# Sheet2.net
KiCad netlist of a schematic drawn in Altium Designer
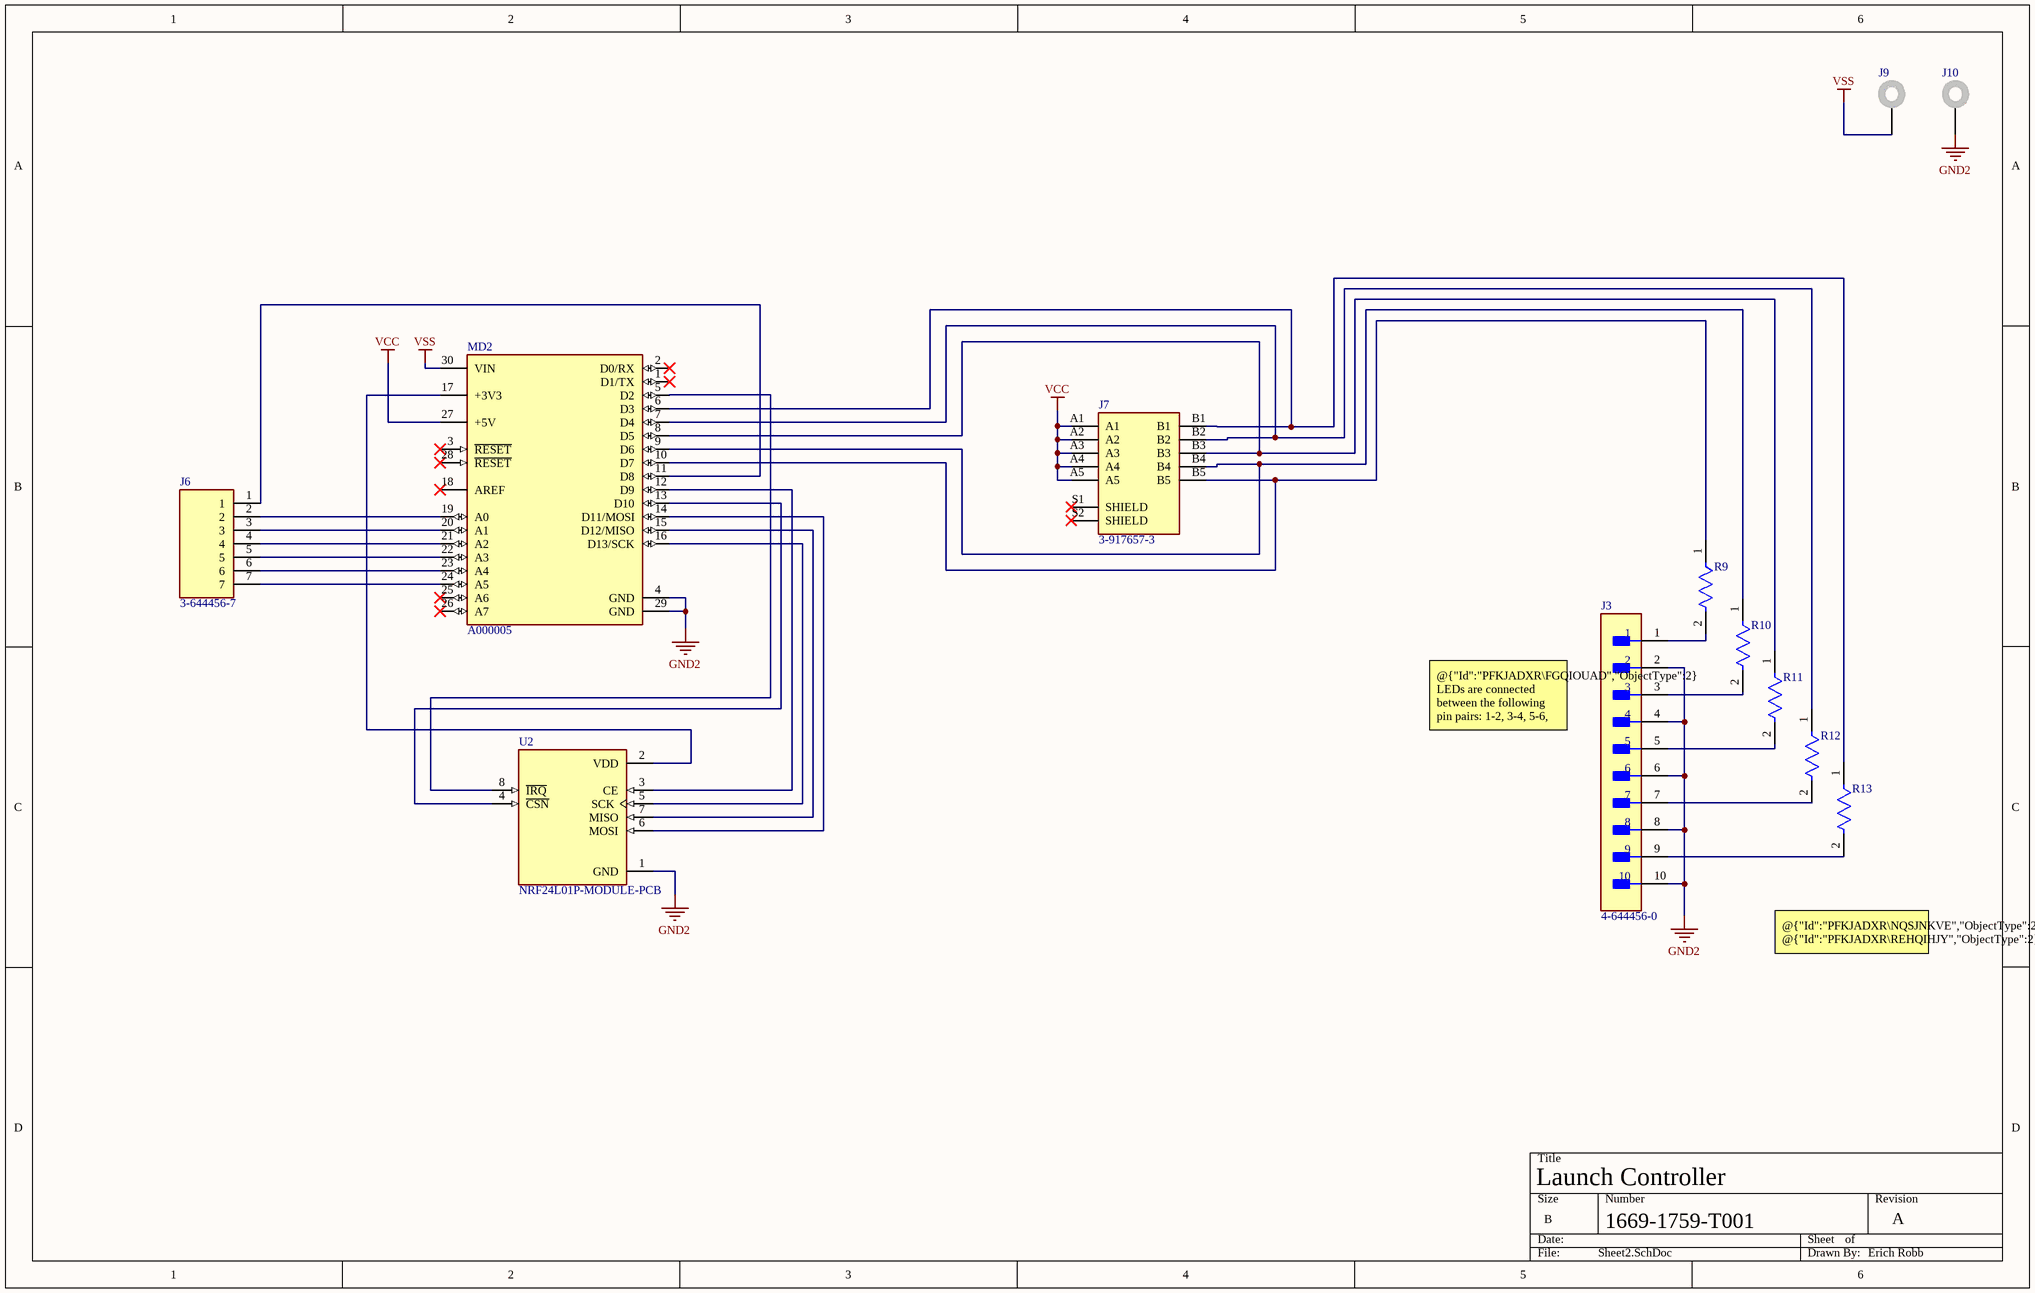
[diagram p0: Sheet2.SchDoc]

(export (version "E")
  (design (tool "Eeschema 10.0.6"))
  (components
    (comp (ref "J3")
      (value "4-644456-0")
      (footprint "FP-4-644456-0-MFG")
      (description "Conn Unshrouded Header HDR 10 POS 2.54mm Solder ST Top Entry Thru-Hole Bag/Box")
      (libsource (lib "Erich Robb") (part "aee40dc8b284c03a16094555aa210be"))
    )
    (comp (ref "J6")
      (value "3-644456-7")
      (footprint "TE_3-644456-7")
      (description "Header; 0.1 in. (Centerline); White (Housing); Polyester; 7; UL 94V-0")
      (fields (field (name "DIGI-KEY_PART_NUMBER") "A31117-ND") (field (name "MF") "TE Connectivity"))
      (libsource (lib "Erich Robb") (part "3-644456-7"))
    )
    (comp (ref "J7")
      (value "3-917657-3")
      (footprint "TE_3-917657-3")
      (libsource (lib "Erich Robb") (part "3-917657-3"))
    )
    (comp (ref "J9")
      (value "575-8")
      (footprint "KSTN-575-8")
      (description "Non-Insulated Jack, Through Hole, RoHS, Bulk")
      (fields (field (name "MANUFACTURER") "Keystone"))
      (libsource (lib "Altium Content Vault") (part "KSTN-575-8"))
    )
    (comp (ref "J10")
      (value "575-8")
      (footprint "KSTN-575-8")
      (description "Non-Insulated Jack, Through Hole, RoHS, Bulk")
      (fields (field (name "MANUFACTURER") "Keystone"))
      (libsource (lib "Altium Content Vault") (part "KSTN-575-8"))
    )
    (comp (ref "MD2")
      (value "A000005")
      (footprint "FP-A000005-MFG")
      (description "ARDUINO NANO ATMEGA328 EVAL BRD")
      (libsource (lib "Altium Content Vault") (part "d190c066e99afd1c6882cf92e11b2cc"))
    )
    (comp (ref "R9")
      (value "CRGCQ1206J330R")
      (footprint "FP-CRGCQ1206-IPC_C")
      (description "CRGCQ1206 330Ω 0.25W 5% ±100ppm/°C 200V")
      (fields (field (name "TOLERANCE") "0.05") (field (name "MANUFACTURER") "TE Connectivity"))
      (libsource (lib "Altium Content Vault") (part "1029c3af85768c4190bb7ad29bc67b5"))
    )
    (comp (ref "R10")
      (value "CRGCQ1206J330R")
      (footprint "FP-CRGCQ1206-IPC_C")
      (description "CRGCQ1206 330Ω 0.25W 5% ±100ppm/°C 200V")
      (fields (field (name "TOLERANCE") "0.05") (field (name "MANUFACTURER") "TE Connectivity"))
      (libsource (lib "Altium Content Vault") (part "1029c3af85768c4190bb7ad29bc67b5"))
    )
    (comp (ref "R11")
      (value "CRGCQ1206J330R")
      (footprint "FP-CRGCQ1206-IPC_C")
      (description "CRGCQ1206 330Ω 0.25W 5% ±100ppm/°C 200V")
      (fields (field (name "TOLERANCE") "0.05") (field (name "MANUFACTURER") "TE Connectivity"))
      (libsource (lib "Altium Content Vault") (part "1029c3af85768c4190bb7ad29bc67b5"))
    )
    (comp (ref "R12")
      (value "CRGCQ1206J330R")
      (footprint "FP-CRGCQ1206-IPC_C")
      (description "CRGCQ1206 330Ω 0.25W 5% ±100ppm/°C 200V")
      (fields (field (name "TOLERANCE") "0.05") (field (name "MANUFACTURER") "TE Connectivity"))
      (libsource (lib "Altium Content Vault") (part "1029c3af85768c4190bb7ad29bc67b5"))
    )
    (comp (ref "R13")
      (value "CRGCQ1206J330R")
      (footprint "FP-CRGCQ1206-IPC_C")
      (description "CRGCQ1206 330Ω 0.25W 5% ±100ppm/°C 200V")
      (fields (field (name "TOLERANCE") "0.05") (field (name "MANUFACTURER") "TE Connectivity"))
      (libsource (lib "Altium Content Vault") (part "1029c3af85768c4190bb7ad29bc67b5"))
    )
    (comp (ref "U2")
      (value "NRF24L01P-MODULE-PCB")
      (footprint "XCVR_NRF24L01P-MODULE-PCB")
      (description "- Transceiver For Use With nRF24L01+")
      (fields (field (name "MF") "Nordic Semiconductor"))
      (libsource (lib "Erich Robb") (part "NRF24L01P-MODULE-PCB"))
    )
  )
  (nets
    (net (code "1") (name "GND2") (class "Default")
      (node (ref "J10") (pin "1") (pinfunction "1_1") (pintype "passive"))
      (node (ref "J3") (pin "10") (pinfunction "10_10") (pintype "passive"))
      (node (ref "J3") (pin "2") (pinfunction "2_2") (pintype "passive"))
      (node (ref "J3") (pin "4") (pinfunction "4_4") (pintype "passive"))
      (node (ref "J3") (pin "6") (pinfunction "6_6") (pintype "passive"))
      (node (ref "J3") (pin "8") (pinfunction "8_8") (pintype "passive"))
      (node (ref "MD2") (pin "29") (pinfunction "GND_29") (pintype "power_in"))
      (node (ref "MD2") (pin "4") (pinfunction "GND_4") (pintype "power_in"))
      (node (ref "U2") (pin "1") (pinfunction "GND_1") (pintype "power_in"))
    )
    (net (code "2") (name "Net-(J3-Pad1)") (class "Default")
      (node (ref "J3") (pin "1") (pinfunction "1_1") (pintype "passive"))
      (node (ref "R9") (pin "2") (pinfunction "2_2") (pintype "passive"))
    )
    (net (code "3") (name "Net-(J3-Pad3)") (class "Default")
      (node (ref "J3") (pin "3") (pinfunction "3_3") (pintype "passive"))
      (node (ref "R10") (pin "2") (pinfunction "2_2") (pintype "passive"))
    )
    (net (code "4") (name "Net-(J3-Pad5)") (class "Default")
      (node (ref "J3") (pin "5") (pinfunction "5_5") (pintype "passive"))
      (node (ref "R11") (pin "2") (pinfunction "2_2") (pintype "passive"))
    )
    (net (code "5") (name "Net-(J3-Pad7)") (class "Default")
      (node (ref "J3") (pin "7") (pinfunction "7_7") (pintype "passive"))
      (node (ref "R12") (pin "2") (pinfunction "2_2") (pintype "passive"))
    )
    (net (code "6") (name "Net-(J3-Pad9)") (class "Default")
      (node (ref "J3") (pin "9") (pinfunction "9_9") (pintype "passive"))
      (node (ref "R13") (pin "2") (pinfunction "2_2") (pintype "passive"))
    )
    (net (code "7") (name "Net-(MD2-+3V3)") (class "Default")
      (node (ref "MD2") (pin "17") (pinfunction "+3V3_17") (pintype "power_in"))
      (node (ref "U2") (pin "2") (pinfunction "VDD_2") (pintype "power_in"))
    )
    (net (code "8") (name "Net-(MD2-A0)") (class "Default")
      (node (ref "J6") (pin "2") (pinfunction "2_2") (pintype "passive"))
      (node (ref "MD2") (pin "19") (pinfunction "A0_19") (pintype "bidirectional"))
    )
    (net (code "9") (name "Net-(MD2-A1)") (class "Default")
      (node (ref "J6") (pin "3") (pinfunction "3_3") (pintype "passive"))
      (node (ref "MD2") (pin "20") (pinfunction "A1_20") (pintype "bidirectional"))
    )
    (net (code "10") (name "Net-(MD2-A2)") (class "Default")
      (node (ref "J6") (pin "4") (pinfunction "4_4") (pintype "passive"))
      (node (ref "MD2") (pin "21") (pinfunction "A2_21") (pintype "bidirectional"))
    )
    (net (code "11") (name "Net-(MD2-A3)") (class "Default")
      (node (ref "J6") (pin "5") (pinfunction "5_5") (pintype "passive"))
      (node (ref "MD2") (pin "22") (pinfunction "A3_22") (pintype "bidirectional"))
    )
    (net (code "12") (name "Net-(MD2-A4)") (class "Default")
      (node (ref "J6") (pin "6") (pinfunction "6_6") (pintype "passive"))
      (node (ref "MD2") (pin "23") (pinfunction "A4_23") (pintype "bidirectional"))
    )
    (net (code "13") (name "Net-(MD2-A5)") (class "Default")
      (node (ref "J6") (pin "7") (pinfunction "7_7") (pintype "passive"))
      (node (ref "MD2") (pin "24") (pinfunction "A5_24") (pintype "bidirectional"))
    )
    (net (code "14") (name "Net-(MD2-D2)") (class "Default")
      (node (ref "MD2") (pin "5") (pinfunction "D2_5") (pintype "bidirectional"))
      (node (ref "U2") (pin "8") (pinfunction "~{IRQ}_8") (pintype "input"))
    )
    (net (code "15") (name "Net-(MD2-D3)") (class "Default")
      (node (ref "J7") (pin "B1") (pinfunction "B1_B1") (pintype "passive"))
      (node (ref "MD2") (pin "6") (pinfunction "D3_6") (pintype "bidirectional"))
      (node (ref "R13") (pin "1") (pinfunction "1_1") (pintype "passive"))
    )
    (net (code "16") (name "Net-(MD2-D4)") (class "Default")
      (node (ref "J7") (pin "B2") (pinfunction "B2_B2") (pintype "passive"))
      (node (ref "MD2") (pin "7") (pinfunction "D4_7") (pintype "bidirectional"))
      (node (ref "R12") (pin "1") (pinfunction "1_1") (pintype "passive"))
    )
    (net (code "17") (name "Net-(MD2-D5)") (class "Default")
      (node (ref "J7") (pin "B3") (pinfunction "B3_B3") (pintype "passive"))
      (node (ref "MD2") (pin "8") (pinfunction "D5_8") (pintype "bidirectional"))
      (node (ref "R11") (pin "1") (pinfunction "1_1") (pintype "passive"))
    )
    (net (code "18") (name "Net-(MD2-D6)") (class "Default")
      (node (ref "J7") (pin "B4") (pinfunction "B4_B4") (pintype "passive"))
      (node (ref "MD2") (pin "9") (pinfunction "D6_9") (pintype "bidirectional"))
      (node (ref "R10") (pin "1") (pinfunction "1_1") (pintype "passive"))
    )
    (net (code "19") (name "Net-(MD2-D7)") (class "Default")
      (node (ref "J7") (pin "B5") (pinfunction "B5_B5") (pintype "passive"))
      (node (ref "MD2") (pin "10") (pinfunction "D7_10") (pintype "bidirectional"))
      (node (ref "R9") (pin "1") (pinfunction "1_1") (pintype "passive"))
    )
    (net (code "20") (name "Net-(MD2-D8)") (class "Default")
      (node (ref "J6") (pin "1") (pinfunction "1_1") (pintype "passive"))
      (node (ref "MD2") (pin "11") (pinfunction "D8_11") (pintype "bidirectional"))
    )
    (net (code "21") (name "Net-(MD2-D9)") (class "Default")
      (node (ref "MD2") (pin "12") (pinfunction "D9_12") (pintype "bidirectional"))
      (node (ref "U2") (pin "3") (pinfunction "CE_3") (pintype "input"))
    )
    (net (code "22") (name "Net-(MD2-D10)") (class "Default")
      (node (ref "MD2") (pin "13") (pinfunction "D10_13") (pintype "bidirectional"))
      (node (ref "U2") (pin "4") (pinfunction "~{CSN}_4") (pintype "input"))
    )
    (net (code "23") (name "Net-(MD2-D11{slash}MOSI)") (class "Default")
      (node (ref "MD2") (pin "14") (pinfunction "D11/MOSI_14") (pintype "bidirectional"))
      (node (ref "U2") (pin "6") (pinfunction "MOSI_6") (pintype "input"))
    )
    (net (code "24") (name "Net-(MD2-D12{slash}MISO)") (class "Default")
      (node (ref "MD2") (pin "15") (pinfunction "D12/MISO_15") (pintype "bidirectional"))
      (node (ref "U2") (pin "7") (pinfunction "MISO_7") (pintype "input"))
    )
    (net (code "25") (name "Net-(MD2-D13{slash}SCK)") (class "Default")
      (node (ref "MD2") (pin "16") (pinfunction "D13/SCK_16") (pintype "bidirectional"))
      (node (ref "U2") (pin "5") (pinfunction "SCK_5") (pintype "input"))
    )
    (net (code "26") (name "VCC") (class "Default")
      (node (ref "J7") (pin "A1") (pinfunction "A1_A1") (pintype "passive"))
      (node (ref "J7") (pin "A2") (pinfunction "A2_A2") (pintype "passive"))
      (node (ref "J7") (pin "A3") (pinfunction "A3_A3") (pintype "passive"))
      (node (ref "J7") (pin "A4") (pinfunction "A4_A4") (pintype "passive"))
      (node (ref "J7") (pin "A5") (pinfunction "A5_A5") (pintype "passive"))
      (node (ref "MD2") (pin "27") (pinfunction "+5V_27") (pintype "power_in"))
    )
    (net (code "27") (name "VSS") (class "Default")
      (node (ref "J9") (pin "1") (pinfunction "1_1") (pintype "passive"))
      (node (ref "MD2") (pin "30") (pinfunction "VIN_30") (pintype "power_in"))
    )
    (net (code "28") (name "unconnected-(J7-SHIELD-PadS1)") (class "Default")
      (node (ref "J7") (pin "S1") (pinfunction "SHIELD_S1") (pintype "passive+no_connect"))
    )
    (net (code "29") (name "unconnected-(J7-SHIELD-PadS2)") (class "Default")
      (node (ref "J7") (pin "S2") (pinfunction "SHIELD_S2") (pintype "passive+no_connect"))
    )
    (net (code "30") (name "unconnected-(MD2-A6-Pad25)") (class "Default")
      (node (ref "MD2") (pin "25") (pinfunction "A6_25") (pintype "bidirectional+no_connect"))
    )
    (net (code "31") (name "unconnected-(MD2-A7-Pad26)") (class "Default")
      (node (ref "MD2") (pin "26") (pinfunction "A7_26") (pintype "bidirectional+no_connect"))
    )
    (net (code "32") (name "unconnected-(MD2-AREF-Pad18)") (class "Default")
      (node (ref "MD2") (pin "18") (pinfunction "AREF_18") (pintype "passive+no_connect"))
    )
    (net (code "33") (name "unconnected-(MD2-D0{slash}RX-Pad2)") (class "Default")
      (node (ref "MD2") (pin "2") (pinfunction "D0/RX_2") (pintype "bidirectional+no_connect"))
    )
    (net (code "34") (name "unconnected-(MD2-D1{slash}TX-Pad1)") (class "Default")
      (node (ref "MD2") (pin "1") (pinfunction "D1/TX_1") (pintype "bidirectional+no_connect"))
    )
    (net (code "35") (name "unconnected-(MD2-~{RESET}-Pad3)") (class "Default")
      (node (ref "MD2") (pin "3") (pinfunction "~{RESET}_3") (pintype "input+no_connect"))
    )
    (net (code "36") (name "unconnected-(MD2-~{RESET}-Pad28)") (class "Default")
      (node (ref "MD2") (pin "28") (pinfunction "~{RESET}_28") (pintype "input+no_connect"))
    )
  )
)
